# interface.net
KiCad netlist of a schematic drawn in Altium Designer
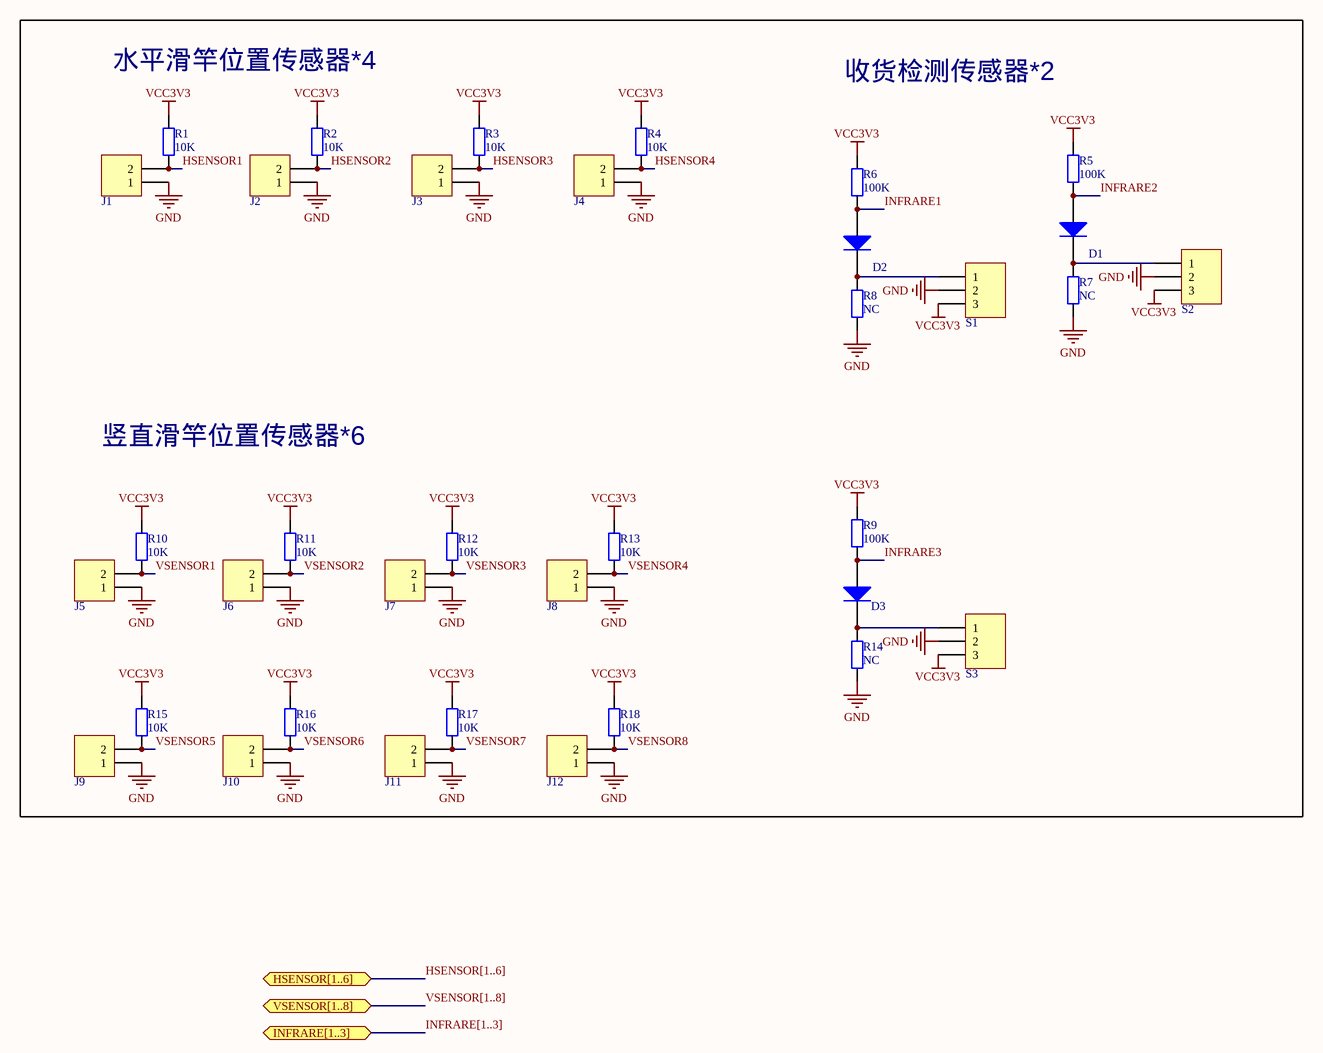
[diagram p0: interface.SchDoc]

(export (version "E")
  (design (tool "Eeschema 10.0.6"))
  (components
    (comp (ref "D1")
      (value "Diode_SOD323")
      (footprint "SOD323_D")
      (description "Default Diode")
      (fields (field (name "PUBLISHER") "Altium Limited"))
      (libsource (lib "阻容晶体管元件") (part "Diode_SOD323"))
    )
    (comp (ref "D2")
      (value "Diode_SOD323")
      (footprint "SOD323_D")
      (description "Default Diode")
      (fields (field (name "PUBLISHER") "Altium Limited"))
      (libsource (lib "阻容晶体管元件") (part "Diode_SOD323"))
    )
    (comp (ref "D3")
      (value "Diode_SOD323")
      (footprint "SOD323_D")
      (description "Default Diode")
      (fields (field (name "PUBLISHER") "Altium Limited"))
      (libsource (lib "阻容晶体管元件") (part "Diode_SOD323"))
    )
    (comp (ref "J1")
      (value "XHB2.54-2PIN-带锁扣")
      (footprint "SIP2")
      (description "Header, 4-Pin")
      (libsource (lib "接插件") (part "XHB2.54-2P直座"))
    )
    (comp (ref "J2")
      (value "XHB2.54-2PIN-带锁扣")
      (footprint "SIP2")
      (description "Header, 4-Pin")
      (libsource (lib "接插件") (part "XHB2.54-2P直座"))
    )
    (comp (ref "J3")
      (value "XHB2.54-2PIN-带锁扣")
      (footprint "SIP2")
      (description "Header, 4-Pin")
      (libsource (lib "接插件") (part "XHB2.54-2P直座"))
    )
    (comp (ref "J4")
      (value "XHB2.54-2PIN-带锁扣")
      (footprint "SIP2")
      (description "Header, 4-Pin")
      (libsource (lib "接插件") (part "XHB2.54-2P直座"))
    )
    (comp (ref "J5")
      (value "XHB2.54-2PIN-带锁扣")
      (footprint "SIP2")
      (description "Header, 4-Pin")
      (libsource (lib "接插件") (part "XHB2.54-2P直座"))
    )
    (comp (ref "J6")
      (value "XHB2.54-2PIN-带锁扣")
      (footprint "SIP2")
      (description "Header, 4-Pin")
      (libsource (lib "接插件") (part "XHB2.54-2P直座"))
    )
    (comp (ref "J7")
      (value "XHB2.54-2PIN-带锁扣")
      (footprint "SIP2")
      (description "Header, 4-Pin")
      (libsource (lib "接插件") (part "XHB2.54-2P直座"))
    )
    (comp (ref "J8")
      (value "XHB2.54-2PIN-带锁扣")
      (footprint "SIP2")
      (description "Header, 4-Pin")
      (libsource (lib "接插件") (part "XHB2.54-2P直座"))
    )
    (comp (ref "J9")
      (value "XHB2.54-2PIN-带锁扣")
      (footprint "SIP2")
      (description "Header, 4-Pin")
      (libsource (lib "接插件") (part "XHB2.54-2P直座"))
    )
    (comp (ref "J10")
      (value "XHB2.54-2PIN-带锁扣")
      (footprint "SIP2")
      (description "Header, 4-Pin")
      (libsource (lib "接插件") (part "XHB2.54-2P直座"))
    )
    (comp (ref "J11")
      (value "XHB2.54-2PIN-带锁扣")
      (footprint "SIP2")
      (description "Header, 4-Pin")
      (libsource (lib "接插件") (part "XHB2.54-2P直座"))
    )
    (comp (ref "J12")
      (value "XHB2.54-2PIN-带锁扣")
      (footprint "SIP2")
      (description "Header, 4-Pin")
      (libsource (lib "接插件") (part "XHB2.54-2P直座"))
    )
    (comp (ref "R1")
      (value "Res_0603")
      (footprint "0603R")
      (description "Resistor")
      (fields (field (name "型号") "10K"))
      (libsource (lib "阻容晶体管元件") (part "Res_0603"))
    )
    (comp (ref "R2")
      (value "Res_0603")
      (footprint "0603R")
      (description "Resistor")
      (fields (field (name "型号") "10K"))
      (libsource (lib "阻容晶体管元件") (part "Res_0603"))
    )
    (comp (ref "R3")
      (value "Res_0603")
      (footprint "0603R")
      (description "Resistor")
      (fields (field (name "型号") "10K"))
      (libsource (lib "阻容晶体管元件") (part "Res_0603"))
    )
    (comp (ref "R4")
      (value "Res_0603")
      (footprint "0603R")
      (description "Resistor")
      (fields (field (name "型号") "10K"))
      (libsource (lib "阻容晶体管元件") (part "Res_0603"))
    )
    (comp (ref "R5")
      (value "Res_0603")
      (footprint "0603R")
      (description "Resistor")
      (fields (field (name "型号") "100K"))
      (libsource (lib "") (part "Res_0603_1"))
    )
    (comp (ref "R6")
      (value "Res_0603")
      (footprint "0603R")
      (description "Resistor")
      (fields (field (name "型号") "100K"))
      (libsource (lib "") (part "Res_0603_1"))
    )
    (comp (ref "R7")
      (value "Res_0603")
      (footprint "0603R")
      (description "Resistor")
      (fields (field (name "型号") "NC"))
      (libsource (lib "") (part "Res_0603_1"))
    )
    (comp (ref "R8")
      (value "Res_0603")
      (footprint "0603R")
      (description "Resistor")
      (fields (field (name "型号") "NC"))
      (libsource (lib "") (part "Res_0603_1"))
    )
    (comp (ref "R9")
      (value "Res_0603")
      (footprint "0603R")
      (description "Resistor")
      (fields (field (name "型号") "100K"))
      (libsource (lib "") (part "Res_0603_1"))
    )
    (comp (ref "R10")
      (value "Res_0603")
      (footprint "0603R")
      (description "Resistor")
      (fields (field (name "型号") "10K"))
      (libsource (lib "阻容晶体管元件") (part "Res_0603"))
    )
    (comp (ref "R11")
      (value "Res_0603")
      (footprint "0603R")
      (description "Resistor")
      (fields (field (name "型号") "10K"))
      (libsource (lib "阻容晶体管元件") (part "Res_0603"))
    )
    (comp (ref "R12")
      (value "Res_0603")
      (footprint "0603R")
      (description "Resistor")
      (fields (field (name "型号") "10K"))
      (libsource (lib "阻容晶体管元件") (part "Res_0603"))
    )
    (comp (ref "R13")
      (value "Res_0603")
      (footprint "0603R")
      (description "Resistor")
      (fields (field (name "型号") "10K"))
      (libsource (lib "阻容晶体管元件") (part "Res_0603"))
    )
    (comp (ref "R14")
      (value "Res_0603")
      (footprint "0603R")
      (description "Resistor")
      (fields (field (name "型号") "NC"))
      (libsource (lib "") (part "Res_0603_1"))
    )
    (comp (ref "R15")
      (value "Res_0603")
      (footprint "0603R")
      (description "Resistor")
      (fields (field (name "型号") "10K"))
      (libsource (lib "阻容晶体管元件") (part "Res_0603"))
    )
    (comp (ref "R16")
      (value "Res_0603")
      (footprint "0603R")
      (description "Resistor")
      (fields (field (name "型号") "10K"))
      (libsource (lib "阻容晶体管元件") (part "Res_0603"))
    )
    (comp (ref "R17")
      (value "Res_0603")
      (footprint "0603R")
      (description "Resistor")
      (fields (field (name "型号") "10K"))
      (libsource (lib "阻容晶体管元件") (part "Res_0603"))
    )
    (comp (ref "R18")
      (value "Res_0603")
      (footprint "0603R")
      (description "Resistor")
      (fields (field (name "型号") "10K"))
      (libsource (lib "阻容晶体管元件") (part "Res_0603"))
    )
    (comp (ref "S1")
      (value "TJC3-2.54直座")
      (footprint "SIP3")
      (description "Header, 3-Pin")
      (libsource (lib "接插件") (part "TJC3-2.54直座"))
    )
    (comp (ref "S2")
      (value "TJC3-2.54直座")
      (footprint "SIP3")
      (description "Header, 3-Pin")
      (libsource (lib "接插件") (part "TJC3-2.54直座"))
    )
    (comp (ref "S3")
      (value "TJC3-2.54直座")
      (footprint "SIP3")
      (description "Header, 3-Pin")
      (libsource (lib "接插件") (part "TJC3-2.54直座"))
    )
  )
  (nets
    (net (code "3") (name "/HSENSOR1") (class "Default")
      (node (ref "J1") (pin "2") (pinfunction "2_2") (pintype "passive"))
      (node (ref "R1") (pin "2") (pinfunction "2_2") (pintype "passive"))
    )
    (net (code "4") (name "/HSENSOR2") (class "Default")
      (node (ref "J2") (pin "2") (pinfunction "2_2") (pintype "passive"))
      (node (ref "R2") (pin "2") (pinfunction "2_2") (pintype "passive"))
    )
    (net (code "5") (name "/HSENSOR3") (class "Default")
      (node (ref "J3") (pin "2") (pinfunction "2_2") (pintype "passive"))
      (node (ref "R3") (pin "2") (pinfunction "2_2") (pintype "passive"))
    )
    (net (code "6") (name "/HSENSOR4") (class "Default")
      (node (ref "J4") (pin "2") (pinfunction "2_2") (pintype "passive"))
      (node (ref "R4") (pin "2") (pinfunction "2_2") (pintype "passive"))
    )
    (net (code "8") (name "/INFRARE1") (class "Default")
      (node (ref "D2") (pin "1") (pinfunction "1_1") (pintype "passive"))
      (node (ref "R6") (pin "1") (pinfunction "1_1") (pintype "passive"))
    )
    (net (code "9") (name "/INFRARE2") (class "Default")
      (node (ref "D1") (pin "1") (pinfunction "1_1") (pintype "passive"))
      (node (ref "R5") (pin "1") (pinfunction "1_1") (pintype "passive"))
    )
    (net (code "10") (name "/INFRARE3") (class "Default")
      (node (ref "D3") (pin "1") (pinfunction "1_1") (pintype "passive"))
      (node (ref "R9") (pin "1") (pinfunction "1_1") (pintype "passive"))
    )
    (net (code "12") (name "/VSENSOR1") (class "Default")
      (node (ref "J5") (pin "2") (pinfunction "2_2") (pintype "passive"))
      (node (ref "R10") (pin "2") (pinfunction "2_2") (pintype "passive"))
    )
    (net (code "13") (name "/VSENSOR2") (class "Default")
      (node (ref "J6") (pin "2") (pinfunction "2_2") (pintype "passive"))
      (node (ref "R11") (pin "2") (pinfunction "2_2") (pintype "passive"))
    )
    (net (code "14") (name "/VSENSOR3") (class "Default")
      (node (ref "J7") (pin "2") (pinfunction "2_2") (pintype "passive"))
      (node (ref "R12") (pin "2") (pinfunction "2_2") (pintype "passive"))
    )
    (net (code "15") (name "/VSENSOR4") (class "Default")
      (node (ref "J8") (pin "2") (pinfunction "2_2") (pintype "passive"))
      (node (ref "R13") (pin "2") (pinfunction "2_2") (pintype "passive"))
    )
    (net (code "16") (name "/VSENSOR5") (class "Default")
      (node (ref "J9") (pin "2") (pinfunction "2_2") (pintype "passive"))
      (node (ref "R15") (pin "2") (pinfunction "2_2") (pintype "passive"))
    )
    (net (code "17") (name "/VSENSOR6") (class "Default")
      (node (ref "J10") (pin "2") (pinfunction "2_2") (pintype "passive"))
      (node (ref "R16") (pin "2") (pinfunction "2_2") (pintype "passive"))
    )
    (net (code "18") (name "/VSENSOR7") (class "Default")
      (node (ref "J11") (pin "2") (pinfunction "2_2") (pintype "passive"))
      (node (ref "R17") (pin "2") (pinfunction "2_2") (pintype "passive"))
    )
    (net (code "19") (name "/VSENSOR8") (class "Default")
      (node (ref "J12") (pin "2") (pinfunction "2_2") (pintype "passive"))
      (node (ref "R18") (pin "2") (pinfunction "2_2") (pintype "passive"))
    )
    (net (code "21") (name "GND") (class "Default")
      (node (ref "J1") (pin "1") (pinfunction "1_1") (pintype "passive"))
      (node (ref "J10") (pin "1") (pinfunction "1_1") (pintype "passive"))
      (node (ref "J11") (pin "1") (pinfunction "1_1") (pintype "passive"))
      (node (ref "J12") (pin "1") (pinfunction "1_1") (pintype "passive"))
      (node (ref "J2") (pin "1") (pinfunction "1_1") (pintype "passive"))
      (node (ref "J3") (pin "1") (pinfunction "1_1") (pintype "passive"))
      (node (ref "J4") (pin "1") (pinfunction "1_1") (pintype "passive"))
      (node (ref "J5") (pin "1") (pinfunction "1_1") (pintype "passive"))
      (node (ref "J6") (pin "1") (pinfunction "1_1") (pintype "passive"))
      (node (ref "J7") (pin "1") (pinfunction "1_1") (pintype "passive"))
      (node (ref "J8") (pin "1") (pinfunction "1_1") (pintype "passive"))
      (node (ref "J9") (pin "1") (pinfunction "1_1") (pintype "passive"))
      (node (ref "R14") (pin "1") (pinfunction "1_1") (pintype "passive"))
      (node (ref "R7") (pin "1") (pinfunction "1_1") (pintype "passive"))
      (node (ref "R8") (pin "1") (pinfunction "1_1") (pintype "passive"))
      (node (ref "S1") (pin "2") (pinfunction "2_2") (pintype "passive"))
      (node (ref "S2") (pin "2") (pinfunction "2_2") (pintype "passive"))
      (node (ref "S3") (pin "2") (pinfunction "2_2") (pintype "passive"))
    )
    (net (code "22") (name "Net-(D1-Pad2)") (class "Default")
      (node (ref "D1") (pin "2") (pinfunction "2_2") (pintype "passive"))
      (node (ref "R7") (pin "2") (pinfunction "2_2") (pintype "passive"))
      (node (ref "S2") (pin "1") (pinfunction "1_1") (pintype "passive"))
    )
    (net (code "23") (name "Net-(D2-Pad2)") (class "Default")
      (node (ref "D2") (pin "2") (pinfunction "2_2") (pintype "passive"))
      (node (ref "R8") (pin "2") (pinfunction "2_2") (pintype "passive"))
      (node (ref "S1") (pin "1") (pinfunction "1_1") (pintype "passive"))
    )
    (net (code "24") (name "Net-(D3-Pad2)") (class "Default")
      (node (ref "D3") (pin "2") (pinfunction "2_2") (pintype "passive"))
      (node (ref "R14") (pin "2") (pinfunction "2_2") (pintype "passive"))
      (node (ref "S3") (pin "1") (pinfunction "1_1") (pintype "passive"))
    )
    (net (code "25") (name "VCC3V3") (class "Default")
      (node (ref "R1") (pin "1") (pinfunction "1_1") (pintype "passive"))
      (node (ref "R10") (pin "1") (pinfunction "1_1") (pintype "passive"))
      (node (ref "R11") (pin "1") (pinfunction "1_1") (pintype "passive"))
      (node (ref "R12") (pin "1") (pinfunction "1_1") (pintype "passive"))
      (node (ref "R13") (pin "1") (pinfunction "1_1") (pintype "passive"))
      (node (ref "R15") (pin "1") (pinfunction "1_1") (pintype "passive"))
      (node (ref "R16") (pin "1") (pinfunction "1_1") (pintype "passive"))
      (node (ref "R17") (pin "1") (pinfunction "1_1") (pintype "passive"))
      (node (ref "R18") (pin "1") (pinfunction "1_1") (pintype "passive"))
      (node (ref "R2") (pin "1") (pinfunction "1_1") (pintype "passive"))
      (node (ref "R3") (pin "1") (pinfunction "1_1") (pintype "passive"))
      (node (ref "R4") (pin "1") (pinfunction "1_1") (pintype "passive"))
      (node (ref "R5") (pin "2") (pinfunction "2_2") (pintype "passive"))
      (node (ref "R6") (pin "2") (pinfunction "2_2") (pintype "passive"))
      (node (ref "R9") (pin "2") (pinfunction "2_2") (pintype "passive"))
      (node (ref "S1") (pin "3") (pinfunction "3_3") (pintype "passive"))
      (node (ref "S2") (pin "3") (pinfunction "3_3") (pintype "passive"))
      (node (ref "S3") (pin "3") (pinfunction "3_3") (pintype "passive"))
    )
  )
)
